# burnin.net
KiCad netlist of a schematic drawn in EAGLE
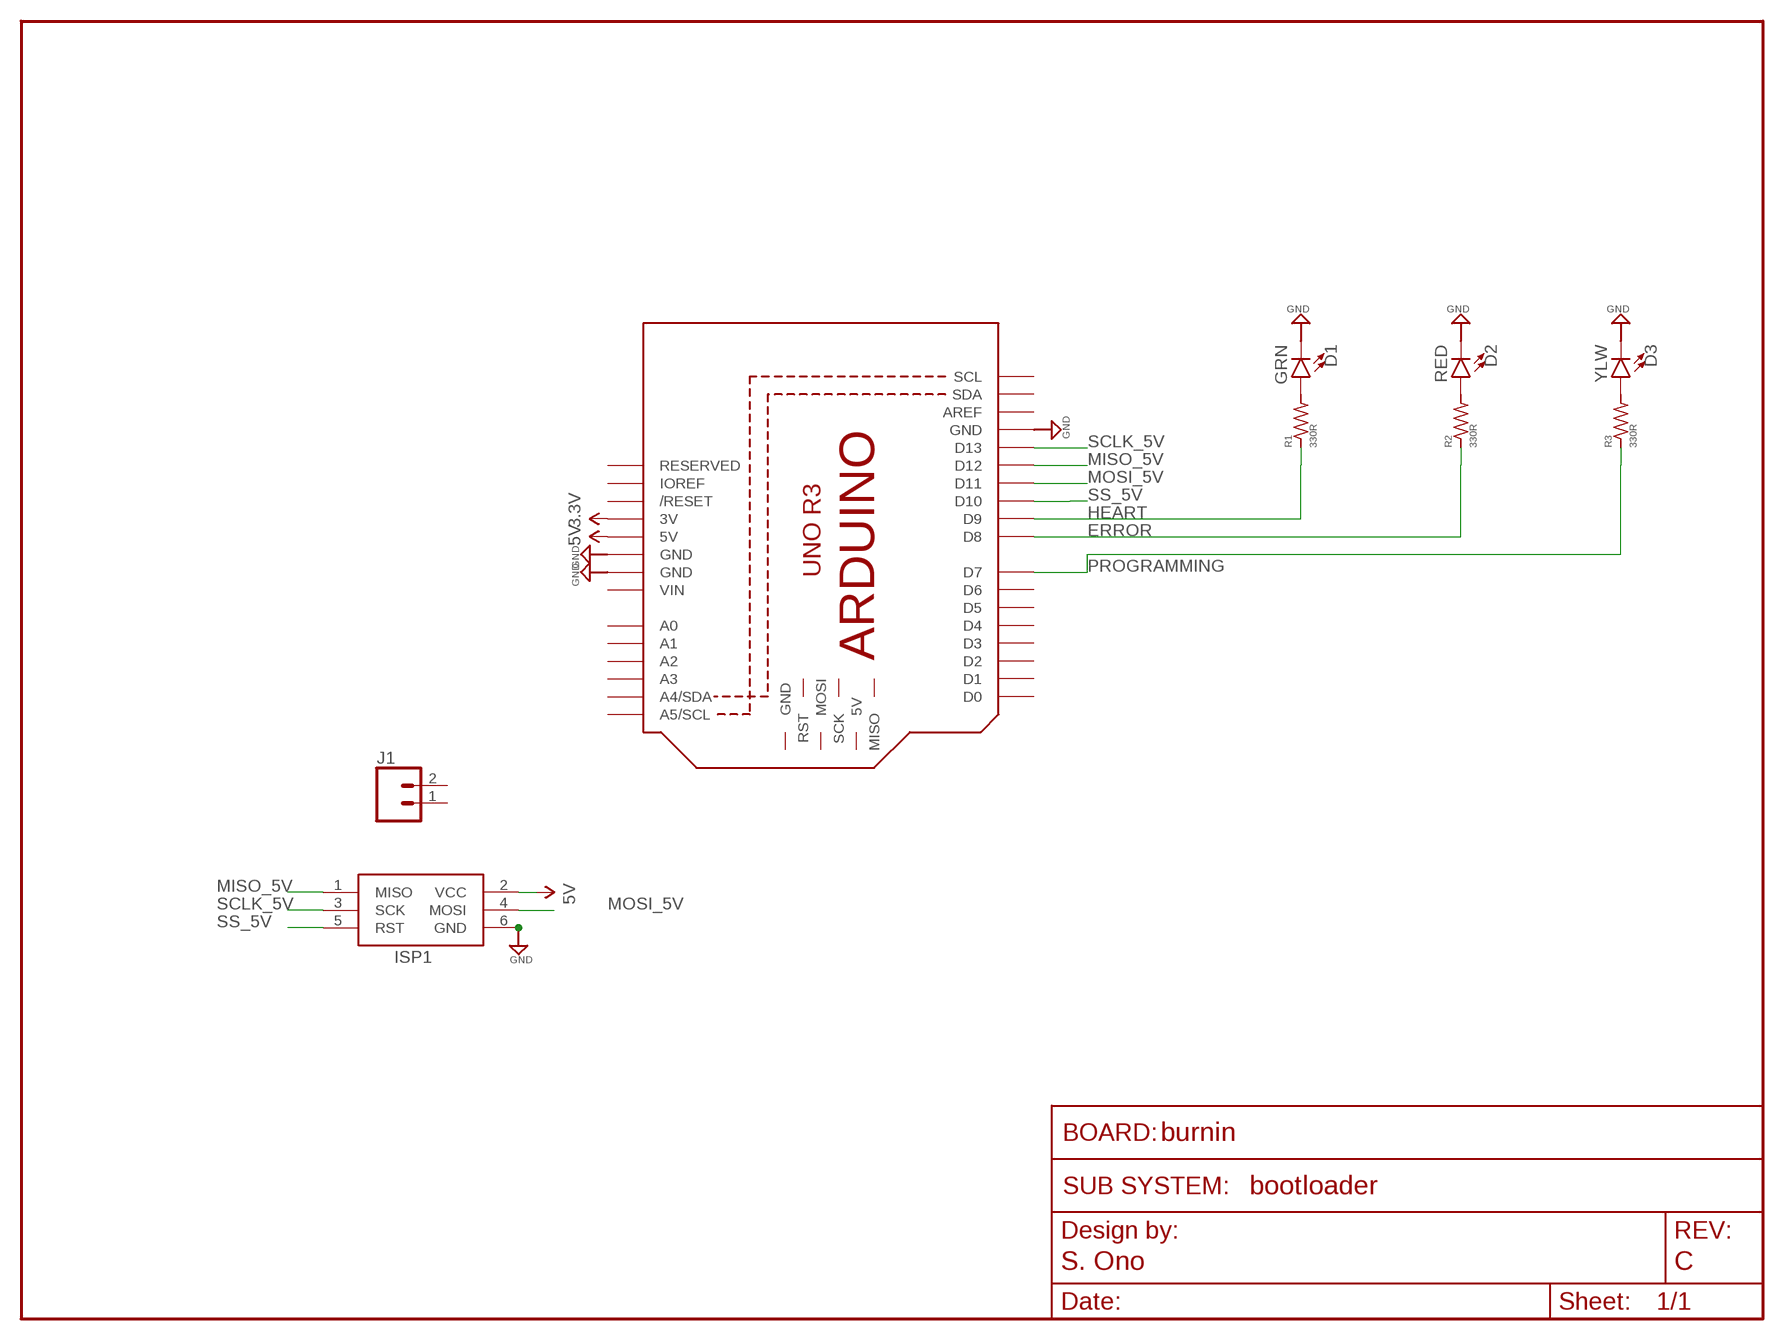
[diagram p0: schematic, sheet 1]

(export (version "E")
  (design (tool "Eeschema 10.0.6"))
  (components
    (comp (ref "D1")
      (value "GRN")
      (footprint "eagle-import:LED-0603")
      (libsource (lib "eagle-import") (part "LED0603"))
    )
    (comp (ref "D2")
      (value "RED")
      (footprint "eagle-import:LED-0603")
      (libsource (lib "eagle-import") (part "LED0603"))
    )
    (comp (ref "D3")
      (value "YLW")
      (footprint "eagle-import:LED-0603")
      (libsource (lib "eagle-import") (part "LED0603"))
    )
    (comp (ref "ISP1")
      (value "AVRISP-6")
      (footprint "eagle-import:AVRISP")
      (libsource (lib "eagle-import") (part "AVRISP-6"))
    )
    (comp (ref "J1")
      (value "CONN_02")
      (footprint "eagle-import:1X02")
      (libsource (lib "eagle-import") (part "CONN_02"))
    )
    (comp (ref "M1")
      (value "ARDUINO_R3_ICSP_NODIM")
      (footprint "eagle-import:ARDUINOR3_ICSP_NODIM")
      (libsource (lib "eagle-import") (part "ARDUINO_R3_ICSP_NODIM"))
    )
    (comp (ref "R1")
      (value "330R")
      (footprint "eagle-import:0603-RES")
      (libsource (lib "eagle-import") (part "R-US_0603"))
    )
    (comp (ref "R2")
      (value "330R")
      (footprint "eagle-import:0603-RES")
      (libsource (lib "eagle-import") (part "R-US_0603"))
    )
    (comp (ref "R3")
      (value "330R")
      (footprint "eagle-import:0603-RES")
      (libsource (lib "eagle-import") (part "R-US_0603"))
    )
  )
  (nets
    (net (code "1") (name "/ERROR") (class "Default")
      (node (ref "M1") (pin "D8") (pinfunction "D8_D8") (pintype "bidirectional"))
      (node (ref "R2") (pin "1") (pinfunction "1_1") (pintype "passive"))
    )
    (net (code "2") (name "/HEART") (class "Default")
      (node (ref "M1") (pin "D9") (pinfunction "D9_D9") (pintype "bidirectional"))
      (node (ref "R1") (pin "1") (pinfunction "1_1") (pintype "passive"))
    )
    (net (code "3") (name "/MISO_5V") (class "Default")
      (node (ref "ISP1") (pin "1") (pinfunction "MISO_1") (pintype "input"))
      (node (ref "M1") (pin "D12") (pinfunction "D12_D12") (pintype "bidirectional"))
    )
    (net (code "4") (name "/MOSI_5V") (class "Default")
      (node (ref "ISP1") (pin "4") (pinfunction "MOSI_4") (pintype "output"))
      (node (ref "M1") (pin "D11") (pinfunction "D11_D11") (pintype "bidirectional"))
    )
    (net (code "5") (name "/PROGRAMMING") (class "Default")
      (node (ref "M1") (pin "D7") (pinfunction "D7_D7") (pintype "bidirectional"))
      (node (ref "R3") (pin "1") (pinfunction "1_1") (pintype "passive"))
    )
    (net (code "6") (name "/SCLK_5V") (class "Default")
      (node (ref "ISP1") (pin "3") (pinfunction "SCK_3") (pintype "output"))
      (node (ref "M1") (pin "D13") (pinfunction "D13_D13") (pintype "bidirectional"))
    )
    (net (code "7") (name "/SS_5V") (class "Default")
      (node (ref "ISP1") (pin "5") (pinfunction "RST_5") (pintype "output"))
      (node (ref "M1") (pin "D10") (pinfunction "D10_D10") (pintype "bidirectional"))
    )
    (net (code "8") (name "/VIN") (class "Default")
      (node (ref "M1") (pin "VIN") (pinfunction "VIN_VIN") (pintype "power_in"))
    )
    (net (code "9") (name "3.3V") (class "Default")
      (node (ref "M1") (pin "3V") (pinfunction "3V_3V") (pintype "power_in"))
    )
    (net (code "10") (name "5V") (class "Default")
      (node (ref "ISP1") (pin "2") (pinfunction "VCC_2") (pintype "power_in"))
      (node (ref "M1") (pin "5V") (pinfunction "5V_5V") (pintype "power_in"))
    )
    (net (code "11") (name "GND") (class "Default")
      (node (ref "D1") (pin "C") (pinfunction "C_C") (pintype "passive"))
      (node (ref "D2") (pin "C") (pinfunction "C_C") (pintype "passive"))
      (node (ref "D3") (pin "C") (pinfunction "C_C") (pintype "passive"))
      (node (ref "ISP1") (pin "6") (pinfunction "GND_6") (pintype "power_in"))
      (node (ref "M1") (pin "GND") (pinfunction "GND_GND") (pintype "power_in"))
      (node (ref "M1") (pin "GND@1") (pinfunction "GND_GND@1") (pintype "power_in"))
      (node (ref "M1") (pin "GND@3") (pinfunction "GND_GND@3") (pintype "power_in"))
    )
    (net (code "12") (name "Net-(D1-PadA)") (class "Default")
      (node (ref "D1") (pin "A") (pinfunction "A_A") (pintype "passive"))
      (node (ref "R1") (pin "2") (pinfunction "2_2") (pintype "passive"))
    )
    (net (code "13") (name "Net-(D2-PadA)") (class "Default")
      (node (ref "D2") (pin "A") (pinfunction "A_A") (pintype "passive"))
      (node (ref "R2") (pin "2") (pinfunction "2_2") (pintype "passive"))
    )
    (net (code "14") (name "Net-(D3-PadA)") (class "Default")
      (node (ref "D3") (pin "A") (pinfunction "A_A") (pintype "passive"))
      (node (ref "R3") (pin "2") (pinfunction "2_2") (pintype "passive"))
    )
    (net (code "15") (name "unconnected-(J1-Pad1)") (class "Default")
      (node (ref "J1") (pin "1") (pinfunction "1_1") (pintype "passive"))
    )
    (net (code "16") (name "unconnected-(J1-Pad2)") (class "Default")
      (node (ref "J1") (pin "2") (pinfunction "2_2") (pintype "passive"))
    )
    (net (code "17") (name "unconnected-(M1-5V-Pad5V_ICSP)") (class "Default")
      (node (ref "M1") (pin "5V_ICSP") (pinfunction "5V_5V_ICSP") (pintype "passive"))
    )
    (net (code "18") (name "unconnected-(M1-A4{slash}SDA-PadA4)") (class "Default")
      (node (ref "M1") (pin "A4") (pinfunction "A4/SDA_A4") (pintype "bidirectional"))
    )
    (net (code "19") (name "unconnected-(M1-A5{slash}SCL-PadA5)") (class "Default")
      (node (ref "M1") (pin "A5") (pinfunction "A5/SCL_A5") (pintype "bidirectional"))
    )
    (net (code "20") (name "unconnected-(M1-GND-PadGND@2)") (class "Default")
      (node (ref "M1") (pin "GND@2") (pinfunction "GND_GND@2") (pintype "passive"))
    )
    (net (code "21") (name "unconnected-(M1-PadA0)") (class "Default")
      (node (ref "M1") (pin "A0") (pinfunction "A0_A0") (pintype "bidirectional"))
    )
    (net (code "22") (name "unconnected-(M1-PadA1)") (class "Default")
      (node (ref "M1") (pin "A1") (pinfunction "A1_A1") (pintype "bidirectional"))
    )
    (net (code "23") (name "unconnected-(M1-PadA2)") (class "Default")
      (node (ref "M1") (pin "A2") (pinfunction "A2_A2") (pintype "bidirectional"))
    )
    (net (code "24") (name "unconnected-(M1-PadA3)") (class "Default")
      (node (ref "M1") (pin "A3") (pinfunction "A3_A3") (pintype "bidirectional"))
    )
    (net (code "25") (name "unconnected-(M1-PadAREF)") (class "Default")
      (node (ref "M1") (pin "AREF") (pinfunction "AREF_AREF") (pintype "bidirectional"))
    )
    (net (code "26") (name "unconnected-(M1-PadD0)") (class "Default")
      (node (ref "M1") (pin "D0") (pinfunction "D0_D0") (pintype "bidirectional"))
    )
    (net (code "27") (name "unconnected-(M1-PadD1)") (class "Default")
      (node (ref "M1") (pin "D1") (pinfunction "D1_D1") (pintype "bidirectional"))
    )
    (net (code "28") (name "unconnected-(M1-PadD2)") (class "Default")
      (node (ref "M1") (pin "D2") (pinfunction "D2_D2") (pintype "bidirectional"))
    )
    (net (code "29") (name "unconnected-(M1-PadD3)") (class "Default")
      (node (ref "M1") (pin "D3") (pinfunction "D3_D3") (pintype "bidirectional"))
    )
    (net (code "30") (name "unconnected-(M1-PadD4)") (class "Default")
      (node (ref "M1") (pin "D4") (pinfunction "D4_D4") (pintype "bidirectional"))
    )
    (net (code "31") (name "unconnected-(M1-PadD5)") (class "Default")
      (node (ref "M1") (pin "D5") (pinfunction "D5_D5") (pintype "bidirectional"))
    )
    (net (code "32") (name "unconnected-(M1-PadD6)") (class "Default")
      (node (ref "M1") (pin "D6") (pinfunction "D6_D6") (pintype "bidirectional"))
    )
    (net (code "33") (name "unconnected-(M1-PadIOREF)") (class "Default")
      (node (ref "M1") (pin "IOREF") (pinfunction "IOREF_IOREF") (pintype "output"))
    )
    (net (code "34") (name "unconnected-(M1-PadMISO)") (class "Default")
      (node (ref "M1") (pin "MISO") (pinfunction "MISO_MISO") (pintype "passive"))
    )
    (net (code "35") (name "unconnected-(M1-PadMOSI)") (class "Default")
      (node (ref "M1") (pin "MOSI") (pinfunction "MOSI_MOSI") (pintype "passive"))
    )
    (net (code "36") (name "unconnected-(M1-PadRESERVED)") (class "Default")
      (node (ref "M1") (pin "RESERVED") (pinfunction "RESERVED_RESERVED") (pintype "no_connect"))
    )
    (net (code "37") (name "unconnected-(M1-PadSCK)") (class "Default")
      (node (ref "M1") (pin "SCK") (pinfunction "SCK_SCK") (pintype "passive"))
    )
    (net (code "38") (name "unconnected-(M1-PadSCL)") (class "Default")
      (node (ref "M1") (pin "SCL") (pinfunction "SCL_SCL") (pintype "bidirectional"))
    )
    (net (code "39") (name "unconnected-(M1-PadSDA)") (class "Default")
      (node (ref "M1") (pin "SDA") (pinfunction "SDA_SDA") (pintype "bidirectional"))
    )
    (net (code "40") (name "unconnected-(M1-RST-PadRESET_ICSP)") (class "Default")
      (node (ref "M1") (pin "RESET_ICSP") (pinfunction "RST_RESET_ICSP") (pintype "passive"))
    )
    (net (code "41") (name "unconnected-(M1-{slash}RESET-PadRESET)") (class "Default")
      (node (ref "M1") (pin "RESET") (pinfunction "/RESET_RESET") (pintype "bidirectional"))
    )
  )
)
